# Mainboard_Encoder_Interface.net
KiCad netlist of a schematic drawn in Altium Designer
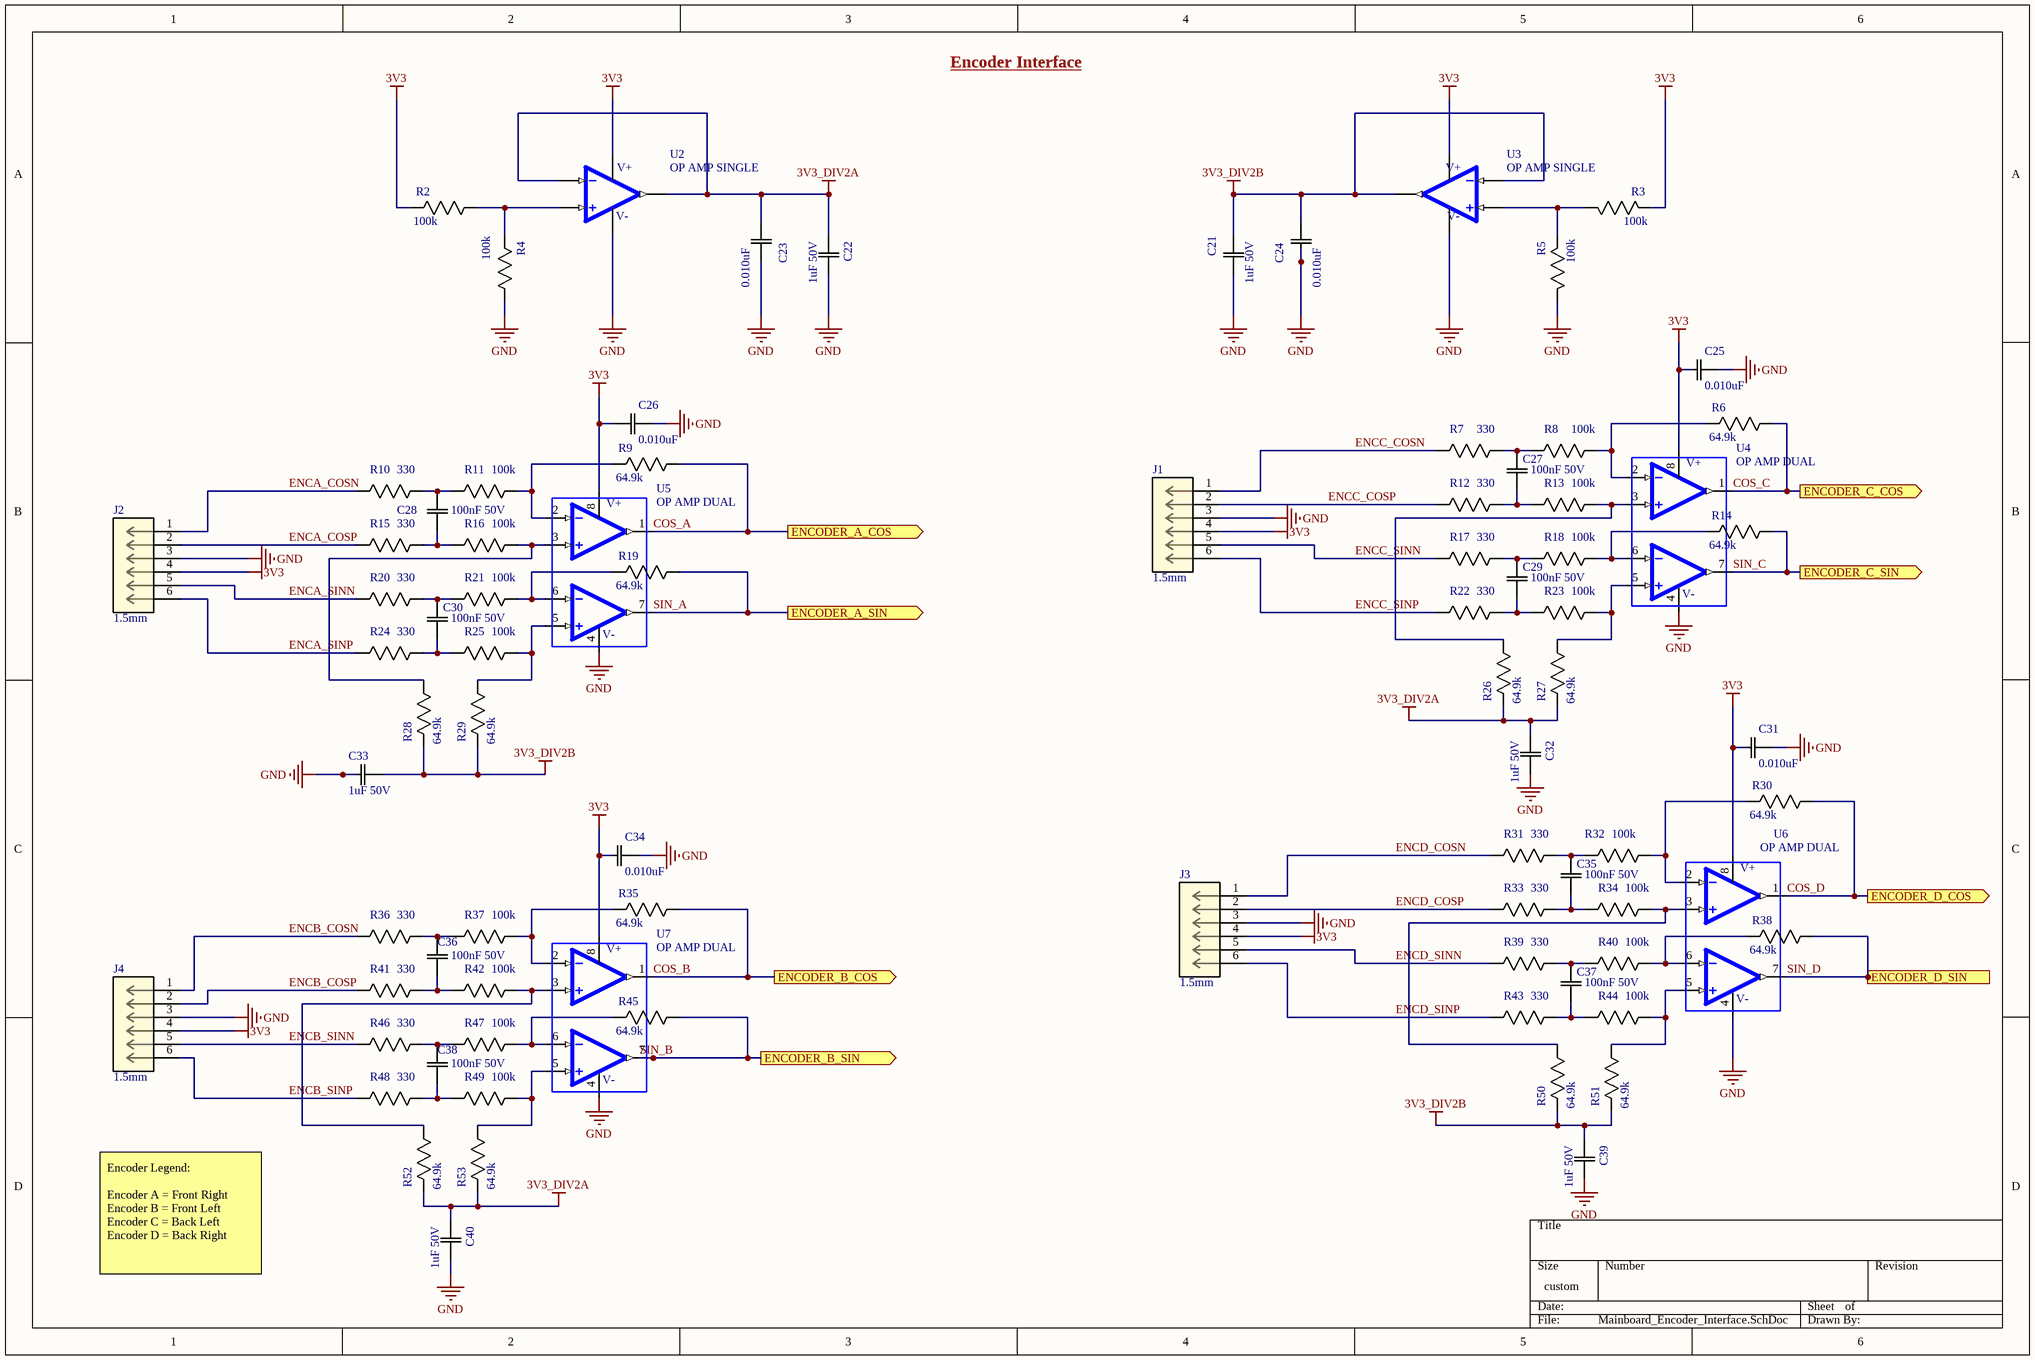
[diagram p0: Mainboard_Encoder_Interface.SchDoc]

(export (version "E")
  (design (tool "Eeschema 10.0.6"))
  (components
    (comp (ref "C21")
      (value "1uF 50V")
      (footprint "0805")
      (description "CAP CER 1UF 50V X7R 0805")
      (fields (field (name "TOLERANCE") "10%"))
      (libsource (lib "AltiumLibraries") (part "CAP 1uF 50V"))
    )
    (comp (ref "C22")
      (value "1uF 50V")
      (footprint "0805")
      (description "CAP CER 1UF 50V X7R 0805")
      (fields (field (name "TOLERANCE") "10%"))
      (libsource (lib "AltiumLibraries") (part "CAP 1uF 50V"))
    )
    (comp (ref "C23")
      (value "0.010uF")
      (footprint "0805")
      (description "CAP CER 0.010UF 50V X7R 0603/0805")
      (fields (field (name "TOLERANCE") "10%"))
      (libsource (lib "AltiumLibraries") (part "CAP 0.010uF 50V"))
    )
    (comp (ref "C24")
      (value "0.010uF")
      (footprint "0805")
      (description "CAP CER 0.010UF 50V X7R 0603/0805")
      (fields (field (name "TOLERANCE") "10%"))
      (libsource (lib "AltiumLibraries") (part "CAP 0.010uF 50V"))
    )
    (comp (ref "C25")
      (value "0.010uF")
      (footprint "0805")
      (description "CAP CER 0.010UF 50V X7R 0603/0805")
      (fields (field (name "TOLERANCE") "10%"))
      (libsource (lib "AltiumLibraries") (part "CAP 0.010uF 50V"))
    )
    (comp (ref "C26")
      (value "0.010uF")
      (footprint "0805")
      (description "CAP CER 0.010UF 50V X7R 0603/0805")
      (fields (field (name "TOLERANCE") "10%"))
      (libsource (lib "AltiumLibraries") (part "CAP 0.010uF 50V"))
    )
    (comp (ref "C27")
      (value "100nF 50V")
      (footprint "0805")
      (description "CAP CER 0.1UF 50V X7R 0805")
      (fields (field (name "TOLERANCE") "10%"))
      (libsource (lib "AltiumLibraries") (part "CAP 100nF 50V"))
    )
    (comp (ref "C28")
      (value "100nF 50V")
      (footprint "0805")
      (description "CAP CER 0.1UF 50V X7R 0805")
      (fields (field (name "TOLERANCE") "10%"))
      (libsource (lib "AltiumLibraries") (part "CAP 100nF 50V"))
    )
    (comp (ref "C29")
      (value "100nF 50V")
      (footprint "0805")
      (description "CAP CER 0.1UF 50V X7R 0805")
      (fields (field (name "TOLERANCE") "10%"))
      (libsource (lib "AltiumLibraries") (part "CAP 100nF 50V"))
    )
    (comp (ref "C30")
      (value "100nF 50V")
      (footprint "0805")
      (description "CAP CER 0.1UF 50V X7R 0805")
      (fields (field (name "TOLERANCE") "10%"))
      (libsource (lib "AltiumLibraries") (part "CAP 100nF 50V"))
    )
    (comp (ref "C31")
      (value "0.010uF")
      (footprint "0805")
      (description "CAP CER 0.010UF 50V X7R 0603/0805")
      (fields (field (name "TOLERANCE") "10%"))
      (libsource (lib "AltiumLibraries") (part "CAP 0.010uF 50V"))
    )
    (comp (ref "C32")
      (value "1uF 50V")
      (footprint "0805")
      (description "CAP CER 1UF 50V X7R 0805")
      (fields (field (name "TOLERANCE") "10%"))
      (libsource (lib "AltiumLibraries") (part "CAP 1uF 50V"))
    )
    (comp (ref "C33")
      (value "1uF 50V")
      (footprint "0805")
      (description "CAP CER 1UF 50V X7R 0805")
      (fields (field (name "TOLERANCE") "10%"))
      (libsource (lib "AltiumLibraries") (part "CAP 1uF 50V"))
    )
    (comp (ref "C34")
      (value "0.010uF")
      (footprint "0805")
      (description "CAP CER 0.010UF 50V X7R 0603/0805")
      (fields (field (name "TOLERANCE") "10%"))
      (libsource (lib "AltiumLibraries") (part "CAP 0.010uF 50V"))
    )
    (comp (ref "C35")
      (value "100nF 50V")
      (footprint "0805")
      (description "CAP CER 0.1UF 50V X7R 0805")
      (fields (field (name "TOLERANCE") "10%"))
      (libsource (lib "AltiumLibraries") (part "CAP 100nF 50V"))
    )
    (comp (ref "C36")
      (value "100nF 50V")
      (footprint "0805")
      (description "CAP CER 0.1UF 50V X7R 0805")
      (fields (field (name "TOLERANCE") "10%"))
      (libsource (lib "AltiumLibraries") (part "CAP 100nF 50V"))
    )
    (comp (ref "C37")
      (value "100nF 50V")
      (footprint "0805")
      (description "CAP CER 0.1UF 50V X7R 0805")
      (fields (field (name "TOLERANCE") "10%"))
      (libsource (lib "AltiumLibraries") (part "CAP 100nF 50V"))
    )
    (comp (ref "C38")
      (value "100nF 50V")
      (footprint "0805")
      (description "CAP CER 0.1UF 50V X7R 0805")
      (fields (field (name "TOLERANCE") "10%"))
      (libsource (lib "AltiumLibraries") (part "CAP 100nF 50V"))
    )
    (comp (ref "C39")
      (value "1uF 50V")
      (footprint "0805")
      (description "CAP CER 1UF 50V X7R 0805")
      (fields (field (name "TOLERANCE") "10%"))
      (libsource (lib "AltiumLibraries") (part "CAP 1uF 50V"))
    )
    (comp (ref "C40")
      (value "1uF 50V")
      (footprint "0805")
      (description "CAP CER 1UF 50V X7R 0805")
      (fields (field (name "TOLERANCE") "10%"))
      (libsource (lib "AltiumLibraries") (part "CAP 1uF 50V"))
    )
    (comp (ref "J1")
      (value "1.5mm")
      (footprint "6POS JST")
      (description "Conn Shrouded Header HDR 6 POS 1.5mm Solder RA Thru-Hole Box")
      (fields (field (name "MANUFACTURER") "JST") (field (name "MANUFACTURER PART NUMBER") "S6B-ZR(LF)(SN)"))
      (libsource (lib "AltiumLibraries") (part "CN 6POS JST RA"))
    )
    (comp (ref "J2")
      (value "1.5mm")
      (footprint "6POS JST")
      (description "Conn Shrouded Header HDR 6 POS 1.5mm Solder RA Thru-Hole Box")
      (fields (field (name "MANUFACTURER") "JST") (field (name "MANUFACTURER PART NUMBER") "S6B-ZR(LF)(SN)"))
      (libsource (lib "AltiumLibraries") (part "CN 6POS JST RA"))
    )
    (comp (ref "J3")
      (value "1.5mm")
      (footprint "6POS JST")
      (description "Conn Shrouded Header HDR 6 POS 1.5mm Solder RA Thru-Hole Box")
      (fields (field (name "MANUFACTURER") "JST") (field (name "MANUFACTURER PART NUMBER") "S6B-ZR(LF)(SN)"))
      (libsource (lib "AltiumLibraries") (part "CN 6POS JST RA"))
    )
    (comp (ref "J4")
      (value "1.5mm")
      (footprint "6POS JST")
      (description "Conn Shrouded Header HDR 6 POS 1.5mm Solder RA Thru-Hole Box")
      (fields (field (name "MANUFACTURER") "JST") (field (name "MANUFACTURER PART NUMBER") "S6B-ZR(LF)(SN)"))
      (libsource (lib "AltiumLibraries") (part "CN 6POS JST RA"))
    )
    (comp (ref "R2")
      (value "100k")
      (footprint "0805")
      (description "RES SMD 100K OHM 1% 1/8W 0805")
      (fields (field (name "TOLERANCE") "1%"))
      (libsource (lib "AltiumLibraries") (part "RES 100k 1/8W - 1%"))
    )
    (comp (ref "R3")
      (value "100k")
      (footprint "0805")
      (description "RES SMD 100K OHM 1% 1/8W 0805")
      (fields (field (name "TOLERANCE") "1%"))
      (libsource (lib "AltiumLibraries") (part "RES 100k 1/8W - 1%"))
    )
    (comp (ref "R4")
      (value "100k")
      (footprint "0805")
      (description "RES SMD 100K OHM 1% 1/8W 0805")
      (fields (field (name "TOLERANCE") "1%"))
      (libsource (lib "AltiumLibraries") (part "RES 100k 1/8W - 1%"))
    )
    (comp (ref "R5")
      (value "100k")
      (footprint "0805")
      (description "RES SMD 100K OHM 1% 1/8W 0805")
      (fields (field (name "TOLERANCE") "1%"))
      (libsource (lib "AltiumLibraries") (part "RES 100k 1/8W - 1%"))
    )
    (comp (ref "R6")
      (value "64.9k")
      (footprint "0805")
      (description "RES SMD 64.9K OHM 1% 1/8W 0805")
      (fields (field (name "TOLERANCE") "1%"))
      (libsource (lib "") (part "RES 64.9k 1/8W_1"))
    )
    (comp (ref "R7")
      (value "330")
      (footprint "0805")
      (description "RES SMD 330 OHM 1% 1/8W 0805")
      (fields (field (name "TOLERANCE") "1%"))
      (libsource (lib "AltiumLibraries") (part "RES 330.0 1/8W - 1%"))
    )
    (comp (ref "R8")
      (value "100k")
      (footprint "0805")
      (description "RES SMD 100K OHM 1% 1/8W 0805")
      (fields (field (name "TOLERANCE") "1%"))
      (libsource (lib "AltiumLibraries") (part "RES 100k 1/8W - 1%"))
    )
    (comp (ref "R9")
      (value "64.9k")
      (footprint "0805")
      (description "RES SMD 64.9K OHM 1% 1/8W 0805")
      (fields (field (name "TOLERANCE") "1%"))
      (libsource (lib "") (part "RES 64.9k 1/8W_1"))
    )
    (comp (ref "R10")
      (value "330")
      (footprint "0805")
      (description "RES SMD 330 OHM 1% 1/8W 0805")
      (fields (field (name "TOLERANCE") "1%"))
      (libsource (lib "AltiumLibraries") (part "RES 330.0 1/8W - 1%"))
    )
    (comp (ref "R11")
      (value "100k")
      (footprint "0805")
      (description "RES SMD 100K OHM 1% 1/8W 0805")
      (fields (field (name "TOLERANCE") "1%"))
      (libsource (lib "AltiumLibraries") (part "RES 100k 1/8W - 1%"))
    )
    (comp (ref "R12")
      (value "330")
      (footprint "0805")
      (description "RES SMD 330 OHM 1% 1/8W 0805")
      (fields (field (name "TOLERANCE") "1%"))
      (libsource (lib "AltiumLibraries") (part "RES 330.0 1/8W - 1%"))
    )
    (comp (ref "R13")
      (value "100k")
      (footprint "0805")
      (description "RES SMD 100K OHM 1% 1/8W 0805")
      (fields (field (name "TOLERANCE") "1%"))
      (libsource (lib "AltiumLibraries") (part "RES 100k 1/8W - 1%"))
    )
    (comp (ref "R14")
      (value "64.9k")
      (footprint "0805")
      (description "RES SMD 64.9K OHM 1% 1/8W 0805")
      (fields (field (name "TOLERANCE") "1%"))
      (libsource (lib "") (part "RES 64.9k 1/8W_1"))
    )
    (comp (ref "R15")
      (value "330")
      (footprint "0805")
      (description "RES SMD 330 OHM 1% 1/8W 0805")
      (fields (field (name "TOLERANCE") "1%"))
      (libsource (lib "AltiumLibraries") (part "RES 330.0 1/8W - 1%"))
    )
    (comp (ref "R16")
      (value "100k")
      (footprint "0805")
      (description "RES SMD 100K OHM 1% 1/8W 0805")
      (fields (field (name "TOLERANCE") "1%"))
      (libsource (lib "AltiumLibraries") (part "RES 100k 1/8W - 1%"))
    )
    (comp (ref "R17")
      (value "330")
      (footprint "0805")
      (description "RES SMD 330 OHM 1% 1/8W 0805")
      (fields (field (name "TOLERANCE") "1%"))
      (libsource (lib "AltiumLibraries") (part "RES 330.0 1/8W - 1%"))
    )
    (comp (ref "R18")
      (value "100k")
      (footprint "0805")
      (description "RES SMD 100K OHM 1% 1/8W 0805")
      (fields (field (name "TOLERANCE") "1%"))
      (libsource (lib "AltiumLibraries") (part "RES 100k 1/8W - 1%"))
    )
    (comp (ref "R19")
      (value "64.9k")
      (footprint "0805")
      (description "RES SMD 64.9K OHM 1% 1/8W 0805")
      (fields (field (name "TOLERANCE") "1%"))
      (libsource (lib "AltiumLibraries") (part "RES 64.9k 1/8W"))
    )
    (comp (ref "R20")
      (value "330")
      (footprint "0805")
      (description "RES SMD 330 OHM 1% 1/8W 0805")
      (fields (field (name "TOLERANCE") "1%"))
      (libsource (lib "AltiumLibraries") (part "RES 330.0 1/8W - 1%"))
    )
    (comp (ref "R21")
      (value "100k")
      (footprint "0805")
      (description "RES SMD 100K OHM 1% 1/8W 0805")
      (fields (field (name "TOLERANCE") "1%"))
      (libsource (lib "AltiumLibraries") (part "RES 100k 1/8W - 1%"))
    )
    (comp (ref "R22")
      (value "330")
      (footprint "0805")
      (description "RES SMD 330 OHM 1% 1/8W 0805")
      (fields (field (name "TOLERANCE") "1%"))
      (libsource (lib "AltiumLibraries") (part "RES 330.0 1/8W - 1%"))
    )
    (comp (ref "R23")
      (value "100k")
      (footprint "0805")
      (description "RES SMD 100K OHM 1% 1/8W 0805")
      (fields (field (name "TOLERANCE") "1%"))
      (libsource (lib "AltiumLibraries") (part "RES 100k 1/8W - 1%"))
    )
    (comp (ref "R24")
      (value "330")
      (footprint "0805")
      (description "RES SMD 330 OHM 1% 1/8W 0805")
      (fields (field (name "TOLERANCE") "1%"))
      (libsource (lib "AltiumLibraries") (part "RES 330.0 1/8W - 1%"))
    )
    (comp (ref "R25")
      (value "100k")
      (footprint "0805")
      (description "RES SMD 100K OHM 1% 1/8W 0805")
      (fields (field (name "TOLERANCE") "1%"))
      (libsource (lib "AltiumLibraries") (part "RES 100k 1/8W - 1%"))
    )
    (comp (ref "R26")
      (value "64.9k")
      (footprint "0805")
      (description "RES SMD 64.9K OHM 1% 1/8W 0805")
      (fields (field (name "TOLERANCE") "1%"))
      (libsource (lib "AltiumLibraries") (part "RES 64.9k 1/8W"))
    )
    (comp (ref "R27")
      (value "64.9k")
      (footprint "0805")
      (description "RES SMD 64.9K OHM 1% 1/8W 0805")
      (fields (field (name "TOLERANCE") "1%"))
      (libsource (lib "AltiumLibraries") (part "RES 64.9k 1/8W"))
    )
    (comp (ref "R28")
      (value "64.9k")
      (footprint "0805")
      (description "RES SMD 64.9K OHM 1% 1/8W 0805")
      (fields (field (name "TOLERANCE") "1%"))
      (libsource (lib "AltiumLibraries") (part "RES 64.9k 1/8W"))
    )
    (comp (ref "R29")
      (value "64.9k")
      (footprint "0805")
      (description "RES SMD 64.9K OHM 1% 1/8W 0805")
      (fields (field (name "TOLERANCE") "1%"))
      (libsource (lib "AltiumLibraries") (part "RES 64.9k 1/8W"))
    )
    (comp (ref "R30")
      (value "64.9k")
      (footprint "0805")
      (description "RES SMD 64.9K OHM 1% 1/8W 0805")
      (fields (field (name "TOLERANCE") "1%"))
      (libsource (lib "") (part "RES 64.9k 1/8W_1"))
    )
    (comp (ref "R31")
      (value "330")
      (footprint "0805")
      (description "RES SMD 330 OHM 1% 1/8W 0805")
      (fields (field (name "TOLERANCE") "1%"))
      (libsource (lib "AltiumLibraries") (part "RES 330.0 1/8W - 1%"))
    )
    (comp (ref "R32")
      (value "100k")
      (footprint "0805")
      (description "RES SMD 100K OHM 1% 1/8W 0805")
      (fields (field (name "TOLERANCE") "1%"))
      (libsource (lib "AltiumLibraries") (part "RES 100k 1/8W - 1%"))
    )
    (comp (ref "R33")
      (value "330")
      (footprint "0805")
      (description "RES SMD 330 OHM 1% 1/8W 0805")
      (fields (field (name "TOLERANCE") "1%"))
      (libsource (lib "AltiumLibraries") (part "RES 330.0 1/8W - 1%"))
    )
    (comp (ref "R34")
      (value "100k")
      (footprint "0805")
      (description "RES SMD 100K OHM 1% 1/8W 0805")
      (fields (field (name "TOLERANCE") "1%"))
      (libsource (lib "AltiumLibraries") (part "RES 100k 1/8W - 1%"))
    )
    (comp (ref "R35")
      (value "64.9k")
      (footprint "0805")
      (description "RES SMD 64.9K OHM 1% 1/8W 0805")
      (fields (field (name "TOLERANCE") "1%"))
      (libsource (lib "") (part "RES 64.9k 1/8W_1"))
    )
    (comp (ref "R36")
      (value "330")
      (footprint "0805")
      (description "RES SMD 330 OHM 1% 1/8W 0805")
      (fields (field (name "TOLERANCE") "1%"))
      (libsource (lib "AltiumLibraries") (part "RES 330.0 1/8W - 1%"))
    )
    (comp (ref "R37")
      (value "100k")
      (footprint "0805")
      (description "RES SMD 100K OHM 1% 1/8W 0805")
      (fields (field (name "TOLERANCE") "1%"))
      (libsource (lib "AltiumLibraries") (part "RES 100k 1/8W - 1%"))
    )
    (comp (ref "R38")
      (value "64.9k")
      (footprint "0805")
      (description "RES SMD 64.9K OHM 1% 1/8W 0805")
      (fields (field (name "TOLERANCE") "1%"))
      (libsource (lib "AltiumLibraries") (part "RES 64.9k 1/8W"))
    )
    (comp (ref "R39")
      (value "330")
      (footprint "0805")
      (description "RES SMD 330 OHM 1% 1/8W 0805")
      (fields (field (name "TOLERANCE") "1%"))
      (libsource (lib "AltiumLibraries") (part "RES 330.0 1/8W - 1%"))
    )
    (comp (ref "R40")
      (value "100k")
      (footprint "0805")
      (description "RES SMD 100K OHM 1% 1/8W 0805")
      (fields (field (name "TOLERANCE") "1%"))
      (libsource (lib "AltiumLibraries") (part "RES 100k 1/8W - 1%"))
    )
    (comp (ref "R41")
      (value "330")
      (footprint "0805")
      (description "RES SMD 330 OHM 1% 1/8W 0805")
      (fields (field (name "TOLERANCE") "1%"))
      (libsource (lib "AltiumLibraries") (part "RES 330.0 1/8W - 1%"))
    )
    (comp (ref "R42")
      (value "100k")
      (footprint "0805")
      (description "RES SMD 100K OHM 1% 1/8W 0805")
      (fields (field (name "TOLERANCE") "1%"))
      (libsource (lib "AltiumLibraries") (part "RES 100k 1/8W - 1%"))
    )
    (comp (ref "R43")
      (value "330")
      (footprint "0805")
      (description "RES SMD 330 OHM 1% 1/8W 0805")
      (fields (field (name "TOLERANCE") "1%"))
      (libsource (lib "AltiumLibraries") (part "RES 330.0 1/8W - 1%"))
    )
    (comp (ref "R44")
      (value "100k")
      (footprint "0805")
      (description "RES SMD 100K OHM 1% 1/8W 0805")
      (fields (field (name "TOLERANCE") "1%"))
      (libsource (lib "AltiumLibraries") (part "RES 100k 1/8W - 1%"))
    )
    (comp (ref "R45")
      (value "64.9k")
      (footprint "0805")
      (description "RES SMD 64.9K OHM 1% 1/8W 0805")
      (fields (field (name "TOLERANCE") "1%"))
      (libsource (lib "AltiumLibraries") (part "RES 64.9k 1/8W"))
    )
    (comp (ref "R46")
      (value "330")
      (footprint "0805")
      (description "RES SMD 330 OHM 1% 1/8W 0805")
      (fields (field (name "TOLERANCE") "1%"))
      (libsource (lib "AltiumLibraries") (part "RES 330.0 1/8W - 1%"))
    )
    (comp (ref "R47")
      (value "100k")
      (footprint "0805")
      (description "RES SMD 100K OHM 1% 1/8W 0805")
      (fields (field (name "TOLERANCE") "1%"))
      (libsource (lib "AltiumLibraries") (part "RES 100k 1/8W - 1%"))
    )
    (comp (ref "R48")
      (value "330")
      (footprint "0805")
      (description "RES SMD 330 OHM 1% 1/8W 0805")
      (fields (field (name "TOLERANCE") "1%"))
      (libsource (lib "AltiumLibraries") (part "RES 330.0 1/8W - 1%"))
    )
    (comp (ref "R49")
      (value "100k")
      (footprint "0805")
      (description "RES SMD 100K OHM 1% 1/8W 0805")
      (fields (field (name "TOLERANCE") "1%"))
      (libsource (lib "AltiumLibraries") (part "RES 100k 1/8W - 1%"))
    )
    (comp (ref "R50")
      (value "64.9k")
      (footprint "0805")
      (description "RES SMD 64.9K OHM 1% 1/8W 0805")
      (fields (field (name "TOLERANCE") "1%"))
      (libsource (lib "AltiumLibraries") (part "RES 64.9k 1/8W"))
    )
    (comp (ref "R51")
      (value "64.9k")
      (footprint "0805")
      (description "RES SMD 64.9K OHM 1% 1/8W 0805")
      (fields (field (name "TOLERANCE") "1%"))
      (libsource (lib "AltiumLibraries") (part "RES 64.9k 1/8W"))
    )
    (comp (ref "R52")
      (value "64.9k")
      (footprint "0805")
      (description "RES SMD 64.9K OHM 1% 1/8W 0805")
      (fields (field (name "TOLERANCE") "1%"))
      (libsource (lib "AltiumLibraries") (part "RES 64.9k 1/8W"))
    )
    (comp (ref "R53")
      (value "64.9k")
      (footprint "0805")
      (description "RES SMD 64.9K OHM 1% 1/8W 0805")
      (fields (field (name "TOLERANCE") "1%"))
      (libsource (lib "AltiumLibraries") (part "RES 64.9k 1/8W"))
    )
    (comp (ref "U2")
      (value "OP AMP SINGLE")
      (footprint "SOT95P280X145-5N")
      (description "ANALOG DEVICES - ADA4505-1ARJZ-R7 - IC, AMPLIF. OPER., R-R, CMOS, SOT23-5")
      (fields
        (field (name "MANUFACTURER") "Analog Devices")
        (field (name "MANUFACTURER PART NUMBER") "ADA4505-1ARJZ-R7")
      )
      (libsource (lib "AltiumLibraries") (part "OP AMP SINGLE"))
    )
    (comp (ref "U3")
      (value "OP AMP SINGLE")
      (footprint "SOT95P280X145-5N")
      (description "ANALOG DEVICES - ADA4505-1ARJZ-R7 - IC, AMPLIF. OPER., R-R, CMOS, SOT23-5")
      (fields
        (field (name "MANUFACTURER") "Analog Devices")
        (field (name "MANUFACTURER PART NUMBER") "ADA4505-1ARJZ-R7")
      )
      (libsource (lib "AltiumLibraries") (part "OP AMP SINGLE"))
    )
    (comp (ref "U4")
      (value "OP AMP DUAL")
      (footprint "8-MSOP")
      (description "IC OPAMP VFB 50KHZ RRO 8MSOP")
      (fields
        (field (name "MANUFACTURER") "Analog Devices")
        (field (name "MANUFACTURER PART NUMBER") "ADA4505-2ARMZ")
      )
      (libsource (lib "AltiumLibraries") (part "OP AMP DUAL"))
    )
    (comp (ref "U5")
      (value "OP AMP DUAL")
      (footprint "8-MSOP")
      (description "IC OPAMP VFB 50KHZ RRO 8MSOP")
      (fields
        (field (name "MANUFACTURER") "Analog Devices")
        (field (name "MANUFACTURER PART NUMBER") "ADA4505-2ARMZ")
      )
      (libsource (lib "AltiumLibraries") (part "OP AMP DUAL"))
    )
    (comp (ref "U6")
      (value "OP AMP DUAL")
      (footprint "8-MSOP")
      (description "IC OPAMP VFB 50KHZ RRO 8MSOP")
      (fields
        (field (name "MANUFACTURER") "Analog Devices")
        (field (name "MANUFACTURER PART NUMBER") "ADA4505-2ARMZ")
      )
      (libsource (lib "AltiumLibraries") (part "OP AMP DUAL"))
    )
    (comp (ref "U7")
      (value "OP AMP DUAL")
      (footprint "8-MSOP")
      (description "IC OPAMP VFB 50KHZ RRO 8MSOP")
      (fields
        (field (name "MANUFACTURER") "Analog Devices")
        (field (name "MANUFACTURER PART NUMBER") "ADA4505-2ARMZ")
      )
      (libsource (lib "AltiumLibraries") (part "OP AMP DUAL"))
    )
  )
  (nets
    (net (code "1") (name "/COS_A") (class "Default")
      (node (ref "R9") (pin "1") (pinfunction "R1_1") (pintype "passive"))
      (node (ref "U5") (pin "1") (pinfunction "OUTA_1") (pintype "output"))
    )
    (net (code "2") (name "/COS_B") (class "Default")
      (node (ref "R35") (pin "1") (pinfunction "R1_1") (pintype "passive"))
      (node (ref "U7") (pin "1") (pinfunction "OUTA_1") (pintype "output"))
    )
    (net (code "3") (name "/COS_C") (class "Default")
      (node (ref "R6") (pin "1") (pinfunction "R1_1") (pintype "passive"))
      (node (ref "U4") (pin "1") (pinfunction "OUTA_1") (pintype "output"))
    )
    (net (code "4") (name "/COS_D") (class "Default")
      (node (ref "R30") (pin "1") (pinfunction "R1_1") (pintype "passive"))
      (node (ref "U6") (pin "1") (pinfunction "OUTA_1") (pintype "output"))
    )
    (net (code "5") (name "/ENCA_COSN") (class "Default")
      (node (ref "J2") (pin "1") (pinfunction "1_1") (pintype "passive"))
      (node (ref "R10") (pin "2") (pinfunction "R2_2") (pintype "passive"))
    )
    (net (code "6") (name "/ENCA_COSP") (class "Default")
      (node (ref "J2") (pin "2") (pinfunction "2_2") (pintype "passive"))
      (node (ref "R15") (pin "2") (pinfunction "R2_2") (pintype "passive"))
    )
    (net (code "7") (name "/ENCA_SINN") (class "Default")
      (node (ref "J2") (pin "5") (pinfunction "5_5") (pintype "passive"))
      (node (ref "R20") (pin "2") (pinfunction "R2_2") (pintype "passive"))
    )
    (net (code "8") (name "/ENCA_SINP") (class "Default")
      (node (ref "J2") (pin "6") (pinfunction "6_6") (pintype "passive"))
      (node (ref "R24") (pin "2") (pinfunction "R2_2") (pintype "passive"))
    )
    (net (code "9") (name "/ENCB_COSN") (class "Default")
      (node (ref "J4") (pin "1") (pinfunction "1_1") (pintype "passive"))
      (node (ref "R36") (pin "2") (pinfunction "R2_2") (pintype "passive"))
    )
    (net (code "10") (name "/ENCB_COSP") (class "Default")
      (node (ref "J4") (pin "2") (pinfunction "2_2") (pintype "passive"))
      (node (ref "R41") (pin "2") (pinfunction "R2_2") (pintype "passive"))
    )
    (net (code "11") (name "/ENCB_SINN") (class "Default")
      (node (ref "J4") (pin "5") (pinfunction "5_5") (pintype "passive"))
      (node (ref "R46") (pin "2") (pinfunction "R2_2") (pintype "passive"))
    )
    (net (code "12") (name "/ENCB_SINP") (class "Default")
      (node (ref "J4") (pin "6") (pinfunction "6_6") (pintype "passive"))
      (node (ref "R48") (pin "2") (pinfunction "R2_2") (pintype "passive"))
    )
    (net (code "13") (name "/ENCC_COSN") (class "Default")
      (node (ref "J1") (pin "1") (pinfunction "1_1") (pintype "passive"))
      (node (ref "R7") (pin "2") (pinfunction "R2_2") (pintype "passive"))
    )
    (net (code "14") (name "/ENCC_COSP") (class "Default")
      (node (ref "J1") (pin "2") (pinfunction "2_2") (pintype "passive"))
      (node (ref "R12") (pin "2") (pinfunction "R2_2") (pintype "passive"))
    )
    (net (code "15") (name "/ENCC_SINN") (class "Default")
      (node (ref "J1") (pin "5") (pinfunction "5_5") (pintype "passive"))
      (node (ref "R17") (pin "2") (pinfunction "R2_2") (pintype "passive"))
    )
    (net (code "16") (name "/ENCC_SINP") (class "Default")
      (node (ref "J1") (pin "6") (pinfunction "6_6") (pintype "passive"))
      (node (ref "R22") (pin "2") (pinfunction "R2_2") (pintype "passive"))
    )
    (net (code "17") (name "/ENCD_COSN") (class "Default")
      (node (ref "J3") (pin "1") (pinfunction "1_1") (pintype "passive"))
      (node (ref "R31") (pin "2") (pinfunction "R2_2") (pintype "passive"))
    )
    (net (code "18") (name "/ENCD_COSP") (class "Default")
      (node (ref "J3") (pin "2") (pinfunction "2_2") (pintype "passive"))
      (node (ref "R33") (pin "2") (pinfunction "R2_2") (pintype "passive"))
    )
    (net (code "19") (name "/ENCD_SINN") (class "Default")
      (node (ref "J3") (pin "5") (pinfunction "5_5") (pintype "passive"))
      (node (ref "R39") (pin "2") (pinfunction "R2_2") (pintype "passive"))
    )
    (net (code "20") (name "/ENCD_SINP") (class "Default")
      (node (ref "J3") (pin "6") (pinfunction "6_6") (pintype "passive"))
      (node (ref "R43") (pin "2") (pinfunction "R2_2") (pintype "passive"))
    )
    (net (code "21") (name "/SIN_A") (class "Default")
      (node (ref "R19") (pin "1") (pinfunction "R1_1") (pintype "passive"))
      (node (ref "U5") (pin "7") (pinfunction "OUTB_7") (pintype "output"))
    )
    (net (code "22") (name "/SIN_B") (class "Default")
      (node (ref "R45") (pin "1") (pinfunction "R1_1") (pintype "passive"))
      (node (ref "U7") (pin "7") (pinfunction "OUTB_7") (pintype "output"))
    )
    (net (code "23") (name "/SIN_C") (class "Default")
      (node (ref "R14") (pin "1") (pinfunction "R1_1") (pintype "passive"))
      (node (ref "U4") (pin "7") (pinfunction "OUTB_7") (pintype "output"))
    )
    (net (code "24") (name "/SIN_D") (class "Default")
      (node (ref "R38") (pin "1") (pinfunction "R1_1") (pintype "passive"))
      (node (ref "U6") (pin "7") (pinfunction "OUTB_7") (pintype "output"))
    )
    (net (code "25") (name "3V3") (class "Default")
      (node (ref "C25") (pin "1") (pinfunction "C1_1") (pintype "passive"))
      (node (ref "C26") (pin "1") (pinfunction "C1_1") (pintype "passive"))
      (node (ref "C31") (pin "1") (pinfunction "C1_1") (pintype "passive"))
      (node (ref "C34") (pin "1") (pinfunction "C1_1") (pintype "passive"))
      (node (ref "J1") (pin "4") (pinfunction "4_4") (pintype "passive"))
      (node (ref "J2") (pin "4") (pinfunction "4_4") (pintype "passive"))
      (node (ref "J3") (pin "4") (pinfunction "4_4") (pintype "passive"))
      (node (ref "J4") (pin "4") (pinfunction "4_4") (pintype "passive"))
      (node (ref "R2") (pin "2") (pinfunction "R2_2") (pintype "passive"))
      (node (ref "R3") (pin "2") (pinfunction "R2_2") (pintype "passive"))
      (node (ref "U2") (pin "5") (pinfunction "V+_5") (pintype "power_in"))
      (node (ref "U3") (pin "5") (pinfunction "V+_5") (pintype "power_in"))
      (node (ref "U4") (pin "8") (pinfunction "V+_8") (pintype "power_in"))
      (node (ref "U5") (pin "8") (pinfunction "V+_8") (pintype "power_in"))
      (node (ref "U6") (pin "8") (pinfunction "V+_8") (pintype "power_in"))
      (node (ref "U7") (pin "8") (pinfunction "V+_8") (pintype "power_in"))
    )
    (net (code "26") (name "3V3_DIV2A") (class "Default")
      (node (ref "C22") (pin "1") (pinfunction "C1_1") (pintype "passive"))
      (node (ref "C23") (pin "1") (pinfunction "C1_1") (pintype "passive"))
      (node (ref "C32") (pin "1") (pinfunction "C1_1") (pintype "passive"))
      (node (ref "C40") (pin "1") (pinfunction "C1_1") (pintype "passive"))
      (node (ref "R26") (pin "2") (pinfunction "R2_2") (pintype "passive"))
      (node (ref "R27") (pin "2") (pinfunction "R2_2") (pintype "passive"))
      (node (ref "R52") (pin "2") (pinfunction "R2_2") (pintype "passive"))
      (node (ref "R53") (pin "2") (pinfunction "R2_2") (pintype "passive"))
      (node (ref "U2") (pin "1") (pinfunction "OUT_1") (pintype "output"))
      (node (ref "U2") (pin "4") (pinfunction "IN-_4") (pintype "input"))
    )
    (net (code "27") (name "3V3_DIV2B") (class "Default")
      (node (ref "C21") (pin "1") (pinfunction "C1_1") (pintype "passive"))
      (node (ref "C24") (pin "1") (pinfunction "C1_1") (pintype "passive"))
      (node (ref "C33") (pin "2") (pinfunction "C2_2") (pintype "passive"))
      (node (ref "C39") (pin "1") (pinfunction "C1_1") (pintype "passive"))
      (node (ref "R28") (pin "2") (pinfunction "R2_2") (pintype "passive"))
      (node (ref "R29") (pin "2") (pinfunction "R2_2") (pintype "passive"))
      (node (ref "R50") (pin "2") (pinfunction "R2_2") (pintype "passive"))
      (node (ref "R51") (pin "2") (pinfunction "R2_2") (pintype "passive"))
      (node (ref "U3") (pin "1") (pinfunction "OUT_1") (pintype "output"))
      (node (ref "U3") (pin "4") (pinfunction "IN-_4") (pintype "input"))
    )
    (net (code "28") (name "GND") (class "Default")
      (node (ref "C21") (pin "2") (pinfunction "C2_2") (pintype "passive"))
      (node (ref "C22") (pin "2") (pinfunction "C2_2") (pintype "passive"))
      (node (ref "C23") (pin "2") (pinfunction "C2_2") (pintype "passive"))
      (node (ref "C24") (pin "2") (pinfunction "C2_2") (pintype "passive"))
      (node (ref "C25") (pin "2") (pinfunction "C2_2") (pintype "passive"))
      (node (ref "C26") (pin "2") (pinfunction "C2_2") (pintype "passive"))
      (node (ref "C31") (pin "2") (pinfunction "C2_2") (pintype "passive"))
      (node (ref "C32") (pin "2") (pinfunction "C2_2") (pintype "passive"))
      (node (ref "C33") (pin "1") (pinfunction "C1_1") (pintype "passive"))
      (node (ref "C34") (pin "2") (pinfunction "C2_2") (pintype "passive"))
      (node (ref "C39") (pin "2") (pinfunction "C2_2") (pintype "passive"))
      (node (ref "C40") (pin "2") (pinfunction "C2_2") (pintype "passive"))
      (node (ref "J1") (pin "3") (pinfunction "3_3") (pintype "passive"))
      (node (ref "J2") (pin "3") (pinfunction "3_3") (pintype "passive"))
      (node (ref "J3") (pin "3") (pinfunction "3_3") (pintype "passive"))
      (node (ref "J4") (pin "3") (pinfunction "3_3") (pintype "passive"))
      (node (ref "R4") (pin "1") (pinfunction "R1_1") (pintype "passive"))
      (node (ref "R5") (pin "1") (pinfunction "R1_1") (pintype "passive"))
      (node (ref "U2") (pin "2") (pinfunction "V-_2") (pintype "power_in"))
      (node (ref "U3") (pin "2") (pinfunction "V-_2") (pintype "power_in"))
      (node (ref "U4") (pin "4") (pinfunction "V-_4") (pintype "power_in"))
      (node (ref "U5") (pin "4") (pinfunction "V-_4") (pintype "power_in"))
      (node (ref "U6") (pin "4") (pinfunction "V-_4") (pintype "power_in"))
      (node (ref "U7") (pin "4") (pinfunction "V-_4") (pintype "power_in"))
    )
    (net (code "29") (name "Net-(C27-C1)") (class "Default")
      (node (ref "C27") (pin "1") (pinfunction "C1_1") (pintype "passive"))
      (node (ref "R7") (pin "1") (pinfunction "R1_1") (pintype "passive"))
      (node (ref "R8") (pin "2") (pinfunction "R2_2") (pintype "passive"))
    )
    (net (code "30") (name "Net-(C27-C2)") (class "Default")
      (node (ref "C27") (pin "2") (pinfunction "C2_2") (pintype "passive"))
      (node (ref "R12") (pin "1") (pinfunction "R1_1") (pintype "passive"))
      (node (ref "R13") (pin "2") (pinfunction "R2_2") (pintype "passive"))
    )
    (net (code "31") (name "Net-(C28-C1)") (class "Default")
      (node (ref "C28") (pin "1") (pinfunction "C1_1") (pintype "passive"))
      (node (ref "R10") (pin "1") (pinfunction "R1_1") (pintype "passive"))
      (node (ref "R11") (pin "2") (pinfunction "R2_2") (pintype "passive"))
    )
    (net (code "32") (name "Net-(C28-C2)") (class "Default")
      (node (ref "C28") (pin "2") (pinfunction "C2_2") (pintype "passive"))
      (node (ref "R15") (pin "1") (pinfunction "R1_1") (pintype "passive"))
      (node (ref "R16") (pin "2") (pinfunction "R2_2") (pintype "passive"))
    )
    (net (code "33") (name "Net-(C29-C1)") (class "Default")
      (node (ref "C29") (pin "1") (pinfunction "C1_1") (pintype "passive"))
      (node (ref "R17") (pin "1") (pinfunction "R1_1") (pintype "passive"))
      (node (ref "R18") (pin "2") (pinfunction "R2_2") (pintype "passive"))
    )
    (net (code "34") (name "Net-(C29-C2)") (class "Default")
      (node (ref "C29") (pin "2") (pinfunction "C2_2") (pintype "passive"))
      (node (ref "R22") (pin "1") (pinfunction "R1_1") (pintype "passive"))
      (node (ref "R23") (pin "2") (pinfunction "R2_2") (pintype "passive"))
    )
    (net (code "35") (name "Net-(C30-C1)") (class "Default")
      (node (ref "C30") (pin "1") (pinfunction "C1_1") (pintype "passive"))
      (node (ref "R20") (pin "1") (pinfunction "R1_1") (pintype "passive"))
      (node (ref "R21") (pin "2") (pinfunction "R2_2") (pintype "passive"))
    )
    (net (code "36") (name "Net-(C30-C2)") (class "Default")
      (node (ref "C30") (pin "2") (pinfunction "C2_2") (pintype "passive"))
      (node (ref "R24") (pin "1") (pinfunction "R1_1") (pintype "passive"))
      (node (ref "R25") (pin "2") (pinfunction "R2_2") (pintype "passive"))
    )
    (net (code "37") (name "Net-(C35-C1)") (class "Default")
      (node (ref "C35") (pin "1") (pinfunction "C1_1") (pintype "passive"))
      (node (ref "R31") (pin "1") (pinfunction "R1_1") (pintype "passive"))
      (node (ref "R32") (pin "2") (pinfunction "R2_2") (pintype "passive"))
    )
    (net (code "38") (name "Net-(C35-C2)") (class "Default")
      (node (ref "C35") (pin "2") (pinfunction "C2_2") (pintype "passive"))
      (node (ref "R33") (pin "1") (pinfunction "R1_1") (pintype "passive"))
      (node (ref "R34") (pin "2") (pinfunction "R2_2") (pintype "passive"))
    )
    (net (code "39") (name "Net-(C36-C1)") (class "Default")
      (node (ref "C36") (pin "1") (pinfunction "C1_1") (pintype "passive"))
      (node (ref "R36") (pin "1") (pinfunction "R1_1") (pintype "passive"))
      (node (ref "R37") (pin "2") (pinfunction "R2_2") (pintype "passive"))
    )
    (net (code "40") (name "Net-(C36-C2)") (class "Default")
      (node (ref "C36") (pin "2") (pinfunction "C2_2") (pintype "passive"))
      (node (ref "R41") (pin "1") (pinfunction "R1_1") (pintype "passive"))
      (node (ref "R42") (pin "2") (pinfunction "R2_2") (pintype "passive"))
    )
    (net (code "41") (name "Net-(C37-C1)") (class "Default")
      (node (ref "C37") (pin "1") (pinfunction "C1_1") (pintype "passive"))
      (node (ref "R39") (pin "1") (pinfunction "R1_1") (pintype "passive"))
      (node (ref "R40") (pin "2") (pinfunction "R2_2") (pintype "passive"))
    )
    (net (code "42") (name "Net-(C37-C2)") (class "Default")
      (node (ref "C37") (pin "2") (pinfunction "C2_2") (pintype "passive"))
      (node (ref "R43") (pin "1") (pinfunction "R1_1") (pintype "passive"))
      (node (ref "R44") (pin "2") (pinfunction "R2_2") (pintype "passive"))
    )
    (net (code "43") (name "Net-(C38-C1)") (class "Default")
      (node (ref "C38") (pin "1") (pinfunction "C1_1") (pintype "passive"))
      (node (ref "R46") (pin "1") (pinfunction "R1_1") (pintype "passive"))
      (node (ref "R47") (pin "2") (pinfunction "R2_2") (pintype "passive"))
    )
    (net (code "44") (name "Net-(C38-C2)") (class "Default")
      (node (ref "C38") (pin "2") (pinfunction "C2_2") (pintype "passive"))
      (node (ref "R48") (pin "1") (pinfunction "R1_1") (pintype "passive"))
      (node (ref "R49") (pin "2") (pinfunction "R2_2") (pintype "passive"))
    )
    (net (code "45") (name "Net-(R2-R1)") (class "Default")
      (node (ref "R2") (pin "1") (pinfunction "R1_1") (pintype "passive"))
      (node (ref "R4") (pin "2") (pinfunction "R2_2") (pintype "passive"))
      (node (ref "U2") (pin "3") (pinfunction "IN+_3") (pintype "input"))
    )
    (net (code "46") (name "Net-(R3-R1)") (class "Default")
      (node (ref "R3") (pin "1") (pinfunction "R1_1") (pintype "passive"))
      (node (ref "R5") (pin "2") (pinfunction "R2_2") (pintype "passive"))
      (node (ref "U3") (pin "3") (pinfunction "IN+_3") (pintype "input"))
    )
    (net (code "47") (name "Net-(R6-R2)") (class "Default")
      (node (ref "R6") (pin "2") (pinfunction "R2_2") (pintype "passive"))
      (node (ref "R8") (pin "1") (pinfunction "R1_1") (pintype "passive"))
      (node (ref "U4") (pin "2") (pinfunction "INA-_2") (pintype "input"))
    )
    (net (code "48") (name "Net-(R11-R1)") (class "Default")
      (node (ref "R11") (pin "1") (pinfunction "R1_1") (pintype "passive"))
      (node (ref "R9") (pin "2") (pinfunction "R2_2") (pintype "passive"))
      (node (ref "U5") (pin "2") (pinfunction "INA-_2") (pintype "input"))
    )
    (net (code "49") (name "Net-(R13-R1)") (class "Default")
      (node (ref "R13") (pin "1") (pinfunction "R1_1") (pintype "passive"))
      (node (ref "R26") (pin "1") (pinfunction "R1_1") (pintype "passive"))
      (node (ref "U4") (pin "3") (pinfunction "INA+_3") (pintype "input"))
    )
    (net (code "50") (name "Net-(R14-R2)") (class "Default")
      (node (ref "R14") (pin "2") (pinfunction "R2_2") (pintype "passive"))
      (node (ref "R18") (pin "1") (pinfunction "R1_1") (pintype "passive"))
      (node (ref "U4") (pin "6") (pinfunction "INB-_6") (pintype "input"))
    )
    (net (code "51") (name "Net-(R16-R1)") (class "Default")
      (node (ref "R16") (pin "1") (pinfunction "R1_1") (pintype "passive"))
      (node (ref "R28") (pin "1") (pinfunction "R1_1") (pintype "passive"))
      (node (ref "U5") (pin "3") (pinfunction "INA+_3") (pintype "input"))
    )
    (net (code "52") (name "Net-(R19-R2)") (class "Default")
      (node (ref "R19") (pin "2") (pinfunction "R2_2") (pintype "passive"))
      (node (ref "R21") (pin "1") (pinfunction "R1_1") (pintype "passive"))
      (node (ref "U5") (pin "6") (pinfunction "INB-_6") (pintype "input"))
    )
    (net (code "53") (name "Net-(R23-R1)") (class "Default")
      (node (ref "R23") (pin "1") (pinfunction "R1_1") (pintype "passive"))
      (node (ref "R27") (pin "1") (pinfunction "R1_1") (pintype "passive"))
      (node (ref "U4") (pin "5") (pinfunction "INB+_5") (pintype "input"))
    )
    (net (code "54") (name "Net-(R25-R1)") (class "Default")
      (node (ref "R25") (pin "1") (pinfunction "R1_1") (pintype "passive"))
      (node (ref "R29") (pin "1") (pinfunction "R1_1") (pintype "passive"))
      (node (ref "U5") (pin "5") (pinfunction "INB+_5") (pintype "input"))
    )
    (net (code "55") (name "Net-(R30-R2)") (class "Default")
      (node (ref "R30") (pin "2") (pinfunction "R2_2") (pintype "passive"))
      (node (ref "R32") (pin "1") (pinfunction "R1_1") (pintype "passive"))
      (node (ref "U6") (pin "2") (pinfunction "INA-_2") (pintype "input"))
    )
    (net (code "56") (name "Net-(R34-R1)") (class "Default")
      (node (ref "R34") (pin "1") (pinfunction "R1_1") (pintype "passive"))
      (node (ref "R50") (pin "1") (pinfunction "R1_1") (pintype "passive"))
      (node (ref "U6") (pin "3") (pinfunction "INA+_3") (pintype "input"))
    )
    (net (code "57") (name "Net-(R35-R2)") (class "Default")
      (node (ref "R35") (pin "2") (pinfunction "R2_2") (pintype "passive"))
      (node (ref "R37") (pin "1") (pinfunction "R1_1") (pintype "passive"))
      (node (ref "U7") (pin "2") (pinfunction "INA-_2") (pintype "input"))
    )
    (net (code "58") (name "Net-(R38-R2)") (class "Default")
      (node (ref "R38") (pin "2") (pinfunction "R2_2") (pintype "passive"))
      (node (ref "R40") (pin "1") (pinfunction "R1_1") (pintype "passive"))
      (node (ref "U6") (pin "6") (pinfunction "INB-_6") (pintype "input"))
    )
    (net (code "59") (name "Net-(R42-R1)") (class "Default")
      (node (ref "R42") (pin "1") (pinfunction "R1_1") (pintype "passive"))
      (node (ref "R52") (pin "1") (pinfunction "R1_1") (pintype "passive"))
      (node (ref "U7") (pin "3") (pinfunction "INA+_3") (pintype "input"))
    )
    (net (code "60") (name "Net-(R44-R1)") (class "Default")
      (node (ref "R44") (pin "1") (pinfunction "R1_1") (pintype "passive"))
      (node (ref "R51") (pin "1") (pinfunction "R1_1") (pintype "passive"))
      (node (ref "U6") (pin "5") (pinfunction "INB+_5") (pintype "input"))
    )
    (net (code "61") (name "Net-(R45-R2)") (class "Default")
      (node (ref "R45") (pin "2") (pinfunction "R2_2") (pintype "passive"))
      (node (ref "R47") (pin "1") (pinfunction "R1_1") (pintype "passive"))
      (node (ref "U7") (pin "6") (pinfunction "INB-_6") (pintype "input"))
    )
    (net (code "62") (name "Net-(R49-R1)") (class "Default")
      (node (ref "R49") (pin "1") (pinfunction "R1_1") (pintype "passive"))
      (node (ref "R53") (pin "1") (pinfunction "R1_1") (pintype "passive"))
      (node (ref "U7") (pin "5") (pinfunction "INB+_5") (pintype "input"))
    )
  )
)
